# NodeMCUProject.net
KiCad netlist of a schematic drawn in Altium Designer
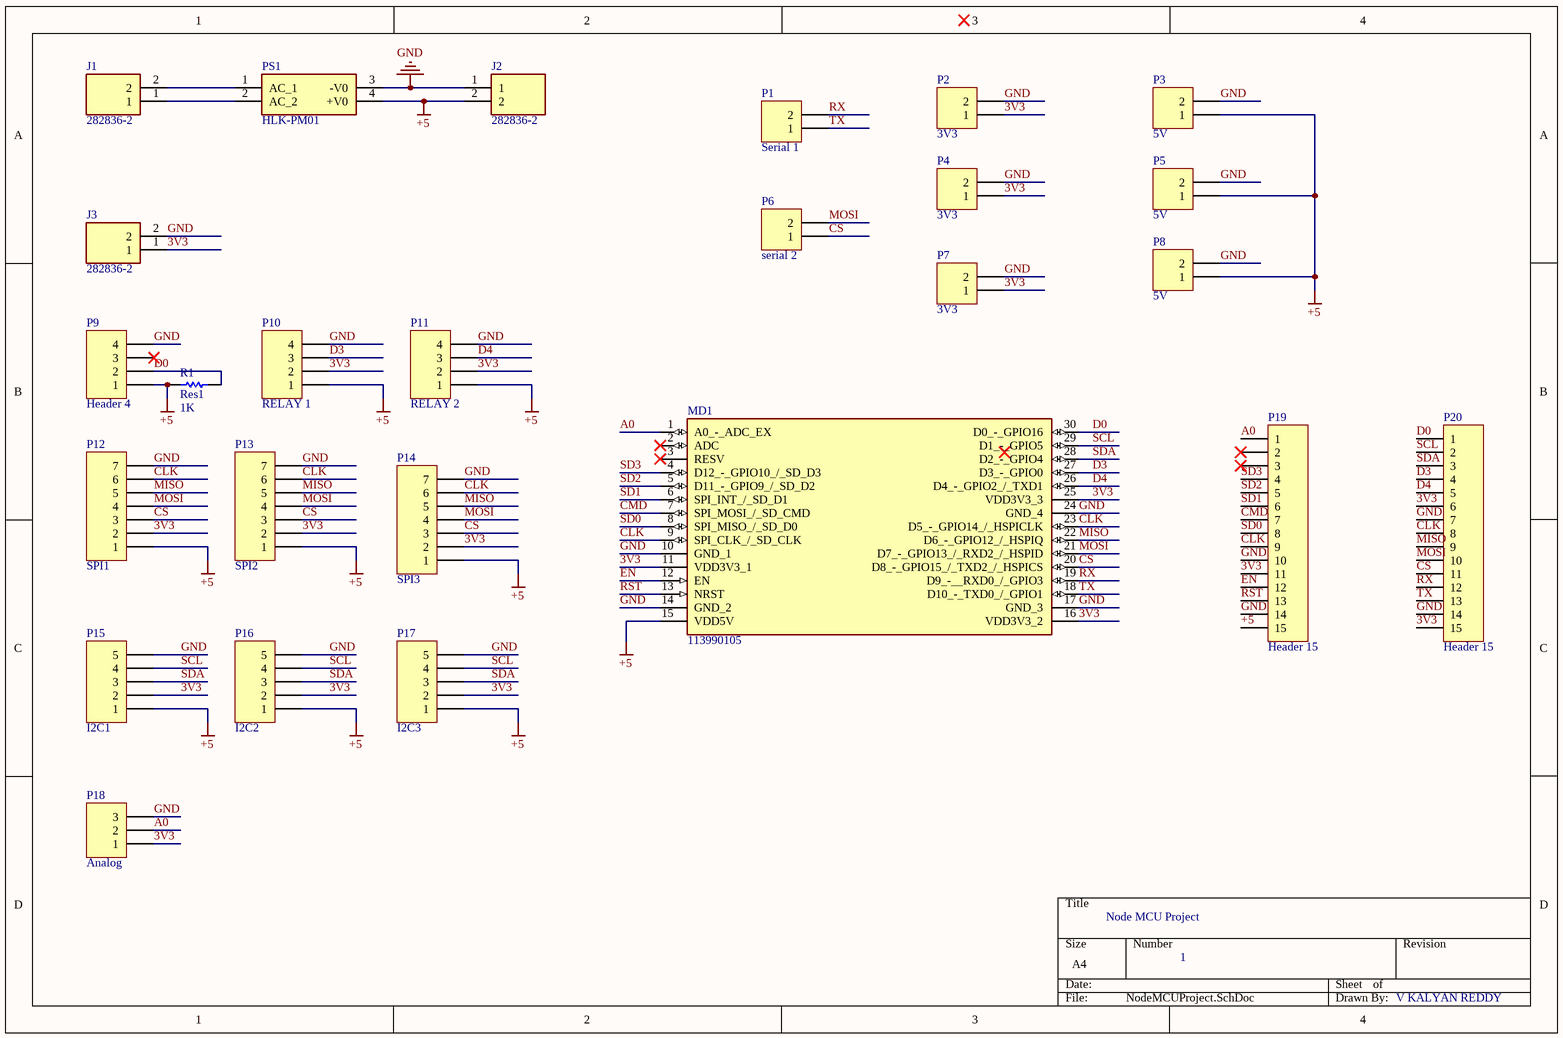
[diagram p0: NodeMCUProject.SchDoc]

(export (version "E")
  (design (tool "Eeschema 10.0.6"))
  (components
    (comp (ref "J1")
      (value "282836-2")
      (footprint "SamacSys:2828362")
      (description "Connector")
      (fields (field (name "MOUSER PART NUMBER") "571-2828362"))
      (libsource (lib "") (part "282836-2_1"))
    )
    (comp (ref "J2")
      (value "282836-2")
      (footprint "SamacSys:2828362")
      (description "Connector")
      (fields (field (name "MOUSER PART NUMBER") "571-2828362"))
      (libsource (lib "*") (part "282836-2"))
    )
    (comp (ref "J3")
      (value "282836-2")
      (footprint "SamacSys:2828362")
      (description "Connector")
      (fields (field (name "MOUSER PART NUMBER") "571-2828362"))
      (libsource (lib "") (part "282836-2_1"))
    )
    (comp (ref "MD1")
      (value "113990105")
      (footprint "SamacSys:113990105")
      (description "Undefined or Miscellaneous")
      (fields (field (name "MOUSER PART NUMBER") "713-113990105"))
      (libsource (lib "*") (part "113990105"))
    )
    (comp (ref "P1")
      (value "Serial 1")
      (footprint "HDR1X2")
      (description "Header, 2-Pin")
      (fields (field (name "PUBLISHER") "Altium Limited"))
      (libsource (lib "Miscellaneous Connectors") (part "Header 2"))
    )
    (comp (ref "P2")
      (value "3V3")
      (footprint "HDR1X2")
      (description "Header, 2-Pin")
      (fields (field (name "PUBLISHER") "Altium Limited"))
      (libsource (lib "Miscellaneous Connectors") (part "Header 2"))
    )
    (comp (ref "P3")
      (value "5V")
      (footprint "HDR1X2")
      (description "Header, 2-Pin")
      (fields (field (name "PUBLISHER") "Altium Limited"))
      (libsource (lib "Miscellaneous Connectors") (part "Header 2"))
    )
    (comp (ref "P4")
      (value "3V3")
      (footprint "HDR1X2")
      (description "Header, 2-Pin")
      (fields (field (name "PUBLISHER") "Altium Limited"))
      (libsource (lib "Miscellaneous Connectors") (part "Header 2"))
    )
    (comp (ref "P5")
      (value "5V")
      (footprint "HDR1X2")
      (description "Header, 2-Pin")
      (fields (field (name "PUBLISHER") "Altium Limited"))
      (libsource (lib "Miscellaneous Connectors") (part "Header 2"))
    )
    (comp (ref "P6")
      (value "serial 2")
      (footprint "HDR1X2")
      (description "Header, 2-Pin")
      (fields (field (name "PUBLISHER") "Altium Limited"))
      (libsource (lib "Miscellaneous Connectors") (part "Header 2"))
    )
    (comp (ref "P7")
      (value "3V3")
      (footprint "HDR1X2")
      (description "Header, 2-Pin")
      (fields (field (name "PUBLISHER") "Altium Limited"))
      (libsource (lib "Miscellaneous Connectors") (part "Header 2"))
    )
    (comp (ref "P8")
      (value "5V")
      (footprint "HDR1X2")
      (description "Header, 2-Pin")
      (fields (field (name "PUBLISHER") "Altium Limited"))
      (libsource (lib "Miscellaneous Connectors") (part "Header 2"))
    )
    (comp (ref "P9")
      (value "Header 4")
      (footprint "HDR1X4")
      (description "Header, 4-Pin")
      (fields (field (name "PUBLISHER") "Altium Limited"))
      (libsource (lib "Miscellaneous Connectors") (part "Header 4"))
    )
    (comp (ref "P10")
      (value "RELAY 1")
      (footprint "HDR1X4")
      (description "Header, 4-Pin")
      (fields (field (name "PUBLISHER") "Altium Limited"))
      (libsource (lib "Miscellaneous Connectors") (part "Header 4"))
    )
    (comp (ref "P11")
      (value "RELAY 2")
      (footprint "HDR1X4")
      (description "Header, 4-Pin")
      (fields (field (name "PUBLISHER") "Altium Limited"))
      (libsource (lib "Miscellaneous Connectors") (part "Header 4"))
    )
    (comp (ref "P12")
      (value "SPI1")
      (footprint "HDR1X7")
      (description "Header, 7-Pin")
      (fields (field (name "PUBLISHER") "Altium Limited"))
      (libsource (lib "Miscellaneous Connectors") (part "Header 7"))
    )
    (comp (ref "P13")
      (value "SPI2")
      (footprint "HDR1X7")
      (description "Header, 7-Pin")
      (fields (field (name "PUBLISHER") "Altium Limited"))
      (libsource (lib "Miscellaneous Connectors") (part "Header 7"))
    )
    (comp (ref "P14")
      (value "SPI3")
      (footprint "HDR1X7")
      (description "Header, 7-Pin")
      (fields (field (name "PUBLISHER") "Altium Limited"))
      (libsource (lib "Miscellaneous Connectors") (part "Header 7"))
    )
    (comp (ref "P15")
      (value "I2C1")
      (footprint "HDR1X5")
      (description "Header, 5-Pin")
      (fields (field (name "PUBLISHER") "Altium Limited"))
      (libsource (lib "Miscellaneous Connectors") (part "Header 5"))
    )
    (comp (ref "P16")
      (value "I2C2")
      (footprint "HDR1X5")
      (description "Header, 5-Pin")
      (fields (field (name "PUBLISHER") "Altium Limited"))
      (libsource (lib "Miscellaneous Connectors") (part "Header 5"))
    )
    (comp (ref "P17")
      (value "I2C3")
      (footprint "HDR1X5")
      (description "Header, 5-Pin")
      (fields (field (name "PUBLISHER") "Altium Limited"))
      (libsource (lib "Miscellaneous Connectors") (part "Header 5"))
    )
    (comp (ref "P18")
      (value "Analog")
      (footprint "HDR1X3")
      (description "Header, 3-Pin")
      (fields (field (name "PUBLISHER") "Altium Limited"))
      (libsource (lib "Miscellaneous Connectors") (part "Header 3"))
    )
    (comp (ref "P19")
      (value "Header 15")
      (footprint "HDR1X15")
      (description "Header, 15-Pin")
      (fields (field (name "PUBLISHER") "Altium Limited"))
      (libsource (lib "Miscellaneous Connectors") (part "Header 15"))
    )
    (comp (ref "P20")
      (value "Header 15")
      (footprint "HDR1X15")
      (description "Header, 15-Pin")
      (fields (field (name "PUBLISHER") "Altium Limited"))
      (libsource (lib "Miscellaneous Connectors") (part "Header 15"))
    )
    (comp (ref "PS1")
      (value "HLK-PM01")
      (footprint "SamacSys:HLKPM01")
      (description "Power Supply")
      (libsource (lib "*") (part "HLK-PM01"))
    )
    (comp (ref "R1")
      (value "Res1")
      (footprint "AXIAL-0.3")
      (description "Resistor")
      (fields (field (name "ALTIUM_VALUE") "1K") (field (name "PUBLISHER") "Altium Limited"))
      (libsource (lib "Miscellaneous Devices") (part "Res1"))
    )
  )
  (nets
    (net (code "1") (name "+5") (class "Default")
      (node (ref "J2") (pin "2") (pinfunction "2_2") (pintype "passive"))
      (node (ref "MD1") (pin "15") (pinfunction "VDD5V_15") (pintype "power_in"))
      (node (ref "P10") (pin "1") (pinfunction "1_1") (pintype "passive"))
      (node (ref "P11") (pin "1") (pinfunction "1_1") (pintype "passive"))
      (node (ref "P12") (pin "1") (pinfunction "1_1") (pintype "passive"))
      (node (ref "P13") (pin "1") (pinfunction "1_1") (pintype "passive"))
      (node (ref "P14") (pin "1") (pinfunction "1_1") (pintype "passive"))
      (node (ref "P15") (pin "1") (pinfunction "1_1") (pintype "passive"))
      (node (ref "P16") (pin "1") (pinfunction "1_1") (pintype "passive"))
      (node (ref "P17") (pin "1") (pinfunction "1_1") (pintype "passive"))
      (node (ref "P19") (pin "15") (pinfunction "15_15") (pintype "passive"))
      (node (ref "P3") (pin "1") (pinfunction "1_1") (pintype "passive"))
      (node (ref "P5") (pin "1") (pinfunction "1_1") (pintype "passive"))
      (node (ref "P8") (pin "1") (pinfunction "1_1") (pintype "passive"))
      (node (ref "P9") (pin "1") (pinfunction "1_1") (pintype "passive"))
      (node (ref "PS1") (pin "4") (pinfunction "+V0_4") (pintype "passive"))
      (node (ref "R1") (pin "1") (pinfunction "1_1") (pintype "passive"))
    )
    (net (code "2") (name "/3V3") (class "Default")
      (node (ref "J3") (pin "1") (pinfunction "1_1") (pintype "passive"))
      (node (ref "MD1") (pin "11") (pinfunction "VDD3V3_1_11") (pintype "power_in"))
      (node (ref "MD1") (pin "16") (pinfunction "VDD3V3_2_16") (pintype "power_in"))
      (node (ref "MD1") (pin "25") (pinfunction "VDD3V3_3_25") (pintype "power_in"))
      (node (ref "P10") (pin "2") (pinfunction "2_2") (pintype "passive"))
      (node (ref "P11") (pin "2") (pinfunction "2_2") (pintype "passive"))
      (node (ref "P12") (pin "2") (pinfunction "2_2") (pintype "passive"))
      (node (ref "P13") (pin "2") (pinfunction "2_2") (pintype "passive"))
      (node (ref "P14") (pin "2") (pinfunction "2_2") (pintype "passive"))
      (node (ref "P15") (pin "2") (pinfunction "2_2") (pintype "passive"))
      (node (ref "P16") (pin "2") (pinfunction "2_2") (pintype "passive"))
      (node (ref "P17") (pin "2") (pinfunction "2_2") (pintype "passive"))
      (node (ref "P18") (pin "1") (pinfunction "1_1") (pintype "passive"))
      (node (ref "P19") (pin "11") (pinfunction "11_11") (pintype "passive"))
      (node (ref "P2") (pin "1") (pinfunction "1_1") (pintype "passive"))
      (node (ref "P20") (pin "15") (pinfunction "15_15") (pintype "passive"))
      (node (ref "P20") (pin "6") (pinfunction "6_6") (pintype "passive"))
      (node (ref "P4") (pin "1") (pinfunction "1_1") (pintype "passive"))
      (node (ref "P7") (pin "1") (pinfunction "1_1") (pintype "passive"))
    )
    (net (code "3") (name "/A0") (class "Default")
      (node (ref "MD1") (pin "1") (pinfunction "A0_-_ADC_EX_1") (pintype "bidirectional"))
      (node (ref "P18") (pin "2") (pinfunction "2_2") (pintype "passive"))
      (node (ref "P19") (pin "1") (pinfunction "1_1") (pintype "passive"))
    )
    (net (code "4") (name "/CLK") (class "Default")
      (node (ref "MD1") (pin "23") (pinfunction "D5_-_GPIO14_/_HSPICLK_23") (pintype "bidirectional"))
      (node (ref "MD1") (pin "9") (pinfunction "SPI_CLK_/_SD_CLK_9") (pintype "bidirectional"))
      (node (ref "P12") (pin "6") (pinfunction "6_6") (pintype "passive"))
      (node (ref "P13") (pin "6") (pinfunction "6_6") (pintype "passive"))
      (node (ref "P14") (pin "6") (pinfunction "6_6") (pintype "passive"))
      (node (ref "P19") (pin "9") (pinfunction "9_9") (pintype "passive"))
      (node (ref "P20") (pin "8") (pinfunction "8_8") (pintype "passive"))
    )
    (net (code "5") (name "/CMD") (class "Default")
      (node (ref "MD1") (pin "7") (pinfunction "SPI_MOSI_/_SD_CMD_7") (pintype "bidirectional"))
      (node (ref "P19") (pin "7") (pinfunction "7_7") (pintype "passive"))
    )
    (net (code "6") (name "/CS") (class "Default")
      (node (ref "MD1") (pin "20") (pinfunction "D8_-_GPIO15_/_TXD2_/_HSPICS_20") (pintype "bidirectional"))
      (node (ref "P12") (pin "3") (pinfunction "3_3") (pintype "passive"))
      (node (ref "P13") (pin "3") (pinfunction "3_3") (pintype "passive"))
      (node (ref "P14") (pin "3") (pinfunction "3_3") (pintype "passive"))
      (node (ref "P20") (pin "11") (pinfunction "11_11") (pintype "passive"))
      (node (ref "P6") (pin "1") (pinfunction "1_1") (pintype "passive"))
    )
    (net (code "7") (name "/D0") (class "Default")
      (node (ref "MD1") (pin "30") (pinfunction "D0_-_GPIO16_30") (pintype "bidirectional"))
      (node (ref "P20") (pin "1") (pinfunction "1_1") (pintype "passive"))
      (node (ref "P9") (pin "2") (pinfunction "2_2") (pintype "passive"))
      (node (ref "R1") (pin "2") (pinfunction "2_2") (pintype "passive"))
    )
    (net (code "8") (name "/D3") (class "Default")
      (node (ref "MD1") (pin "27") (pinfunction "D3_-_GPIO0_27") (pintype "bidirectional"))
      (node (ref "P10") (pin "3") (pinfunction "3_3") (pintype "passive"))
      (node (ref "P20") (pin "4") (pinfunction "4_4") (pintype "passive"))
    )
    (net (code "9") (name "/D4") (class "Default")
      (node (ref "MD1") (pin "26") (pinfunction "D4_-_GPIO2_/_TXD1_26") (pintype "bidirectional"))
      (node (ref "P11") (pin "3") (pinfunction "3_3") (pintype "passive"))
      (node (ref "P20") (pin "5") (pinfunction "5_5") (pintype "passive"))
    )
    (net (code "10") (name "/EN") (class "Default")
      (node (ref "MD1") (pin "12") (pinfunction "EN_12") (pintype "input"))
      (node (ref "P19") (pin "12") (pinfunction "12_12") (pintype "passive"))
    )
    (net (code "11") (name "/MISO") (class "Default")
      (node (ref "MD1") (pin "22") (pinfunction "D6_-_GPIO12_/_HSPIQ_22") (pintype "bidirectional"))
      (node (ref "P12") (pin "5") (pinfunction "5_5") (pintype "passive"))
      (node (ref "P13") (pin "5") (pinfunction "5_5") (pintype "passive"))
      (node (ref "P14") (pin "5") (pinfunction "5_5") (pintype "passive"))
      (node (ref "P20") (pin "9") (pinfunction "9_9") (pintype "passive"))
    )
    (net (code "12") (name "/MOSI") (class "Default")
      (node (ref "MD1") (pin "21") (pinfunction "D7_-_GPIO13_/_RXD2_/_HSPID_21") (pintype "bidirectional"))
      (node (ref "P12") (pin "4") (pinfunction "4_4") (pintype "passive"))
      (node (ref "P13") (pin "4") (pinfunction "4_4") (pintype "passive"))
      (node (ref "P14") (pin "4") (pinfunction "4_4") (pintype "passive"))
      (node (ref "P20") (pin "10") (pinfunction "10_10") (pintype "passive"))
      (node (ref "P6") (pin "2") (pinfunction "2_2") (pintype "passive"))
    )
    (net (code "13") (name "/RST") (class "Default")
      (node (ref "MD1") (pin "13") (pinfunction "NRST_13") (pintype "input"))
      (node (ref "P19") (pin "13") (pinfunction "13_13") (pintype "passive"))
    )
    (net (code "14") (name "/RX") (class "Default")
      (node (ref "MD1") (pin "19") (pinfunction "D9_-__RXD0_/_GPIO3_19") (pintype "bidirectional"))
      (node (ref "P1") (pin "2") (pinfunction "2_2") (pintype "passive"))
      (node (ref "P20") (pin "12") (pinfunction "12_12") (pintype "passive"))
    )
    (net (code "15") (name "/SCL") (class "Default")
      (node (ref "MD1") (pin "29") (pinfunction "D1_-_GPIO5_29") (pintype "bidirectional"))
      (node (ref "P15") (pin "4") (pinfunction "4_4") (pintype "passive"))
      (node (ref "P16") (pin "4") (pinfunction "4_4") (pintype "passive"))
      (node (ref "P17") (pin "4") (pinfunction "4_4") (pintype "passive"))
      (node (ref "P20") (pin "2") (pinfunction "2_2") (pintype "passive"))
    )
    (net (code "16") (name "/SD0") (class "Default")
      (node (ref "MD1") (pin "8") (pinfunction "SPI_MISO_/_SD_D0_8") (pintype "bidirectional"))
      (node (ref "P19") (pin "8") (pinfunction "8_8") (pintype "passive"))
    )
    (net (code "17") (name "/SD1") (class "Default")
      (node (ref "MD1") (pin "6") (pinfunction "SPI_INT_/_SD_D1_6") (pintype "bidirectional"))
      (node (ref "P19") (pin "6") (pinfunction "6_6") (pintype "passive"))
    )
    (net (code "18") (name "/SD2") (class "Default")
      (node (ref "MD1") (pin "5") (pinfunction "D11_-_GPIO9_/_SD_D2_5") (pintype "bidirectional"))
      (node (ref "P19") (pin "5") (pinfunction "5_5") (pintype "passive"))
    )
    (net (code "19") (name "/SD3") (class "Default")
      (node (ref "MD1") (pin "4") (pinfunction "D12_-_GPIO10_/_SD_D3_4") (pintype "bidirectional"))
      (node (ref "P19") (pin "4") (pinfunction "4_4") (pintype "passive"))
    )
    (net (code "20") (name "/SDA") (class "Default")
      (node (ref "MD1") (pin "28") (pinfunction "D2_-_GPIO4_28") (pintype "bidirectional"))
      (node (ref "P15") (pin "3") (pinfunction "3_3") (pintype "passive"))
      (node (ref "P16") (pin "3") (pinfunction "3_3") (pintype "passive"))
      (node (ref "P17") (pin "3") (pinfunction "3_3") (pintype "passive"))
      (node (ref "P20") (pin "3") (pinfunction "3_3") (pintype "passive"))
    )
    (net (code "21") (name "/TX") (class "Default")
      (node (ref "MD1") (pin "18") (pinfunction "D10_-_TXD0_/_GPIO1_18") (pintype "bidirectional"))
      (node (ref "P1") (pin "1") (pinfunction "1_1") (pintype "passive"))
      (node (ref "P20") (pin "13") (pinfunction "13_13") (pintype "passive"))
    )
    (net (code "22") (name "GND") (class "Default")
      (node (ref "J2") (pin "1") (pinfunction "1_1") (pintype "passive"))
      (node (ref "J3") (pin "2") (pinfunction "2_2") (pintype "passive"))
      (node (ref "MD1") (pin "10") (pinfunction "GND_1_10") (pintype "power_in"))
      (node (ref "MD1") (pin "14") (pinfunction "GND_2_14") (pintype "power_in"))
      (node (ref "MD1") (pin "17") (pinfunction "GND_3_17") (pintype "power_in"))
      (node (ref "MD1") (pin "24") (pinfunction "GND_4_24") (pintype "power_in"))
      (node (ref "P10") (pin "4") (pinfunction "4_4") (pintype "passive"))
      (node (ref "P11") (pin "4") (pinfunction "4_4") (pintype "passive"))
      (node (ref "P12") (pin "7") (pinfunction "7_7") (pintype "passive"))
      (node (ref "P13") (pin "7") (pinfunction "7_7") (pintype "passive"))
      (node (ref "P14") (pin "7") (pinfunction "7_7") (pintype "passive"))
      (node (ref "P15") (pin "5") (pinfunction "5_5") (pintype "passive"))
      (node (ref "P16") (pin "5") (pinfunction "5_5") (pintype "passive"))
      (node (ref "P17") (pin "5") (pinfunction "5_5") (pintype "passive"))
      (node (ref "P18") (pin "3") (pinfunction "3_3") (pintype "passive"))
      (node (ref "P19") (pin "10") (pinfunction "10_10") (pintype "passive"))
      (node (ref "P19") (pin "14") (pinfunction "14_14") (pintype "passive"))
      (node (ref "P2") (pin "2") (pinfunction "2_2") (pintype "passive"))
      (node (ref "P20") (pin "14") (pinfunction "14_14") (pintype "passive"))
      (node (ref "P20") (pin "7") (pinfunction "7_7") (pintype "passive"))
      (node (ref "P3") (pin "2") (pinfunction "2_2") (pintype "passive"))
      (node (ref "P4") (pin "2") (pinfunction "2_2") (pintype "passive"))
      (node (ref "P5") (pin "2") (pinfunction "2_2") (pintype "passive"))
      (node (ref "P7") (pin "2") (pinfunction "2_2") (pintype "passive"))
      (node (ref "P8") (pin "2") (pinfunction "2_2") (pintype "passive"))
      (node (ref "P9") (pin "4") (pinfunction "4_4") (pintype "passive"))
      (node (ref "PS1") (pin "3") (pinfunction "-V0_3") (pintype "passive"))
    )
    (net (code "23") (name "Net-(PS1-AC_1)") (class "Default")
      (node (ref "J1") (pin "2") (pinfunction "2_2") (pintype "passive"))
      (node (ref "PS1") (pin "1") (pinfunction "AC_1_1") (pintype "passive"))
    )
    (net (code "24") (name "Net-(PS1-AC_2)") (class "Default")
      (node (ref "J1") (pin "1") (pinfunction "1_1") (pintype "passive"))
      (node (ref "PS1") (pin "2") (pinfunction "AC_2_2") (pintype "passive"))
    )
    (net (code "25") (name "unconnected-(MD1-ADC-Pad2)") (class "Default")
      (node (ref "MD1") (pin "2") (pinfunction "ADC_2") (pintype "bidirectional+no_connect"))
    )
    (net (code "26") (name "unconnected-(MD1-RESV-Pad3)") (class "Default")
      (node (ref "MD1") (pin "3") (pinfunction "RESV_3") (pintype "passive+no_connect"))
    )
    (net (code "27") (name "unconnected-(P9-Pad3)") (class "Default")
      (node (ref "P9") (pin "3") (pinfunction "3_3") (pintype "passive+no_connect"))
    )
    (net (code "28") (name "unconnected-(P19-Pad2)") (class "Default")
      (node (ref "P19") (pin "2") (pinfunction "2_2") (pintype "passive+no_connect"))
    )
    (net (code "29") (name "unconnected-(P19-Pad3)") (class "Default")
      (node (ref "P19") (pin "3") (pinfunction "3_3") (pintype "passive+no_connect"))
    )
  )
)
